# MagnetAdapter.net
KiCad netlist of a schematic drawn in EAGLE
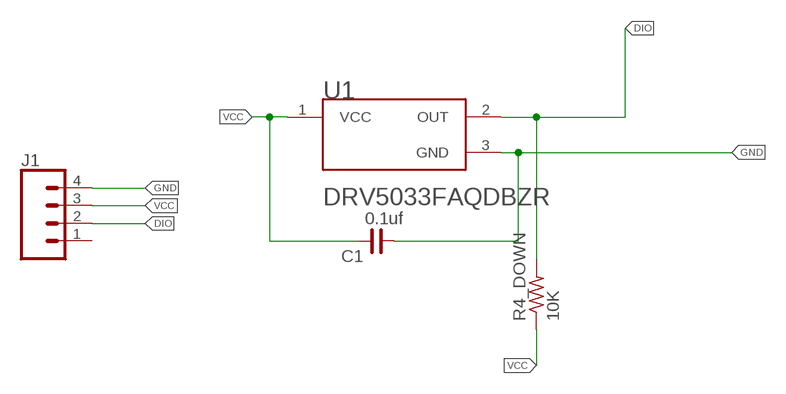
[diagram p0: schematic, sheet 1]

(export (version "E")
  (design (tool "Eeschema 10.0.6"))
  (components
    (comp (ref "C1")
      (value "0.1uf")
      (footprint "eagle-import:C0805")
      (libsource (lib "eagle-import") (part "C_0805"))
    )
    (comp (ref "J1")
      (value "CONN_041X04_NO_SILK")
      (footprint "eagle-import:1X04_NO_SILK")
      (libsource (lib "eagle-import") (part "CONN_041X04_NO_SILK"))
    )
    (comp (ref "R4_DOWN")
      (value "10K")
      (footprint "eagle-import:M0805")
      (libsource (lib "eagle-import") (part "R-US_M0805"))
    )
    (comp (ref "U1")
      (value "TEXAS_INSTRUMENTS_DRV5033FAQDBZRTEXAS_INSTRUMENTS_DRV5033FAQDBZR_0_0")
      (footprint "eagle-import:TEXAS_INSTRUMENTS_DRV5033FAQDBZR_0")
      (fields
        (field (name "DIGIKEY_PART_NUMBER") "296-44589-1-ND")
        (field (name "MF") "Texas Instruments")
        (field (name "MOUSER_PART_NUMBER") "595-DRV5033FAQDBZR")
      )
      (libsource (lib "eagle-import") (part "TEXAS_INSTRUMENTS_DRV5033FAQDBZRTEXAS_INSTRUMENTS_DRV5033FAQDBZR_0_0"))
    )
  )
  (nets
    (net (code "1") (name "DIO") (class "Default")
      (node (ref "J1") (pin "2") (pinfunction "2_2") (pintype "passive"))
      (node (ref "R4_DOWN") (pin "2") (pinfunction "2_2") (pintype "passive"))
      (node (ref "U1") (pin "2") (pinfunction "OUT_2") (pintype "output"))
    )
    (net (code "2") (name "GND") (class "Default")
      (node (ref "C1") (pin "1") (pinfunction "1_1") (pintype "passive"))
      (node (ref "J1") (pin "4") (pinfunction "4_4") (pintype "passive"))
      (node (ref "U1") (pin "3") (pinfunction "GND_3") (pintype "power_in"))
    )
    (net (code "3") (name "VCC") (class "Default")
      (node (ref "C1") (pin "2") (pinfunction "2_2") (pintype "passive"))
      (node (ref "J1") (pin "3") (pinfunction "3_3") (pintype "passive"))
      (node (ref "R4_DOWN") (pin "1") (pinfunction "1_1") (pintype "passive"))
      (node (ref "U1") (pin "1") (pinfunction "VCC_1") (pintype "power_in"))
    )
    (net (code "4") (name "unconnected-(J1-Pad1)") (class "Default")
      (node (ref "J1") (pin "1") (pinfunction "1_1") (pintype "passive"))
    )
  )
)
